# sa-22c-microsemi-powerboard.net
KiCad netlist of a schematic drawn in EAGLE
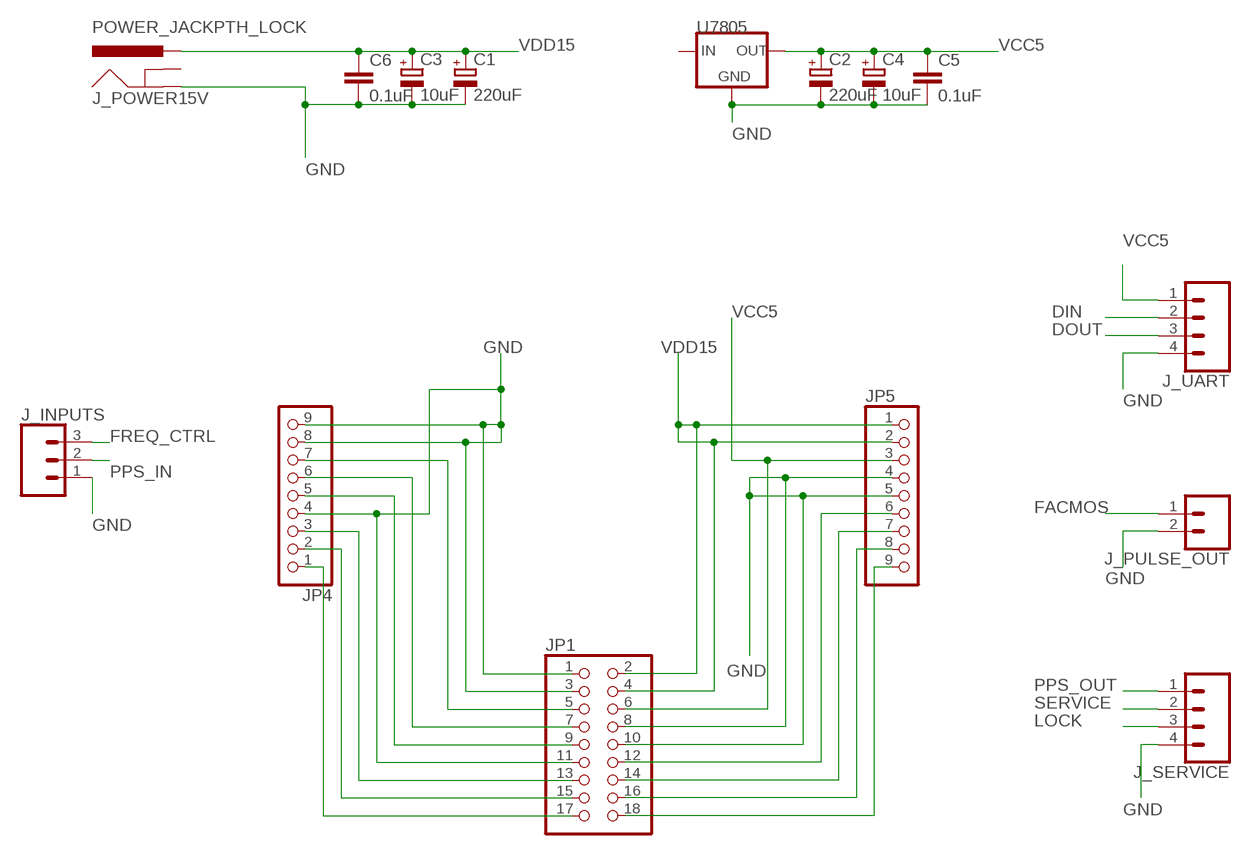
[diagram p0: schematic, sheet 1]

(export (version "E")
  (design (tool "Eeschema 10.0.6"))
  (components
    (comp (ref "C1")
      (value "220uF")
      (footprint "eagle-import:153CLV-1014")
      (libsource (lib "eagle-import") (part "CPOL-EU153CLV-1014"))
    )
    (comp (ref "C2")
      (value "220uF")
      (footprint "eagle-import:153CLV-1014")
      (libsource (lib "eagle-import") (part "CPOL-EU153CLV-1014"))
    )
    (comp (ref "C3")
      (value "10uF")
      (footprint "eagle-import:E2,5-6")
      (libsource (lib "eagle-import") (part "CPOL-EUE2.5-6"))
    )
    (comp (ref "C4")
      (value "10uF")
      (footprint "eagle-import:E2,5-6")
      (libsource (lib "eagle-import") (part "CPOL-EUE2.5-6"))
    )
    (comp (ref "C5")
      (value "0.1uF")
      (footprint "eagle-import:C050-024X044")
      (libsource (lib "eagle-import") (part "C-EU050-024X044"))
    )
    (comp (ref "C6")
      (value "0.1uF")
      (footprint "eagle-import:C050-024X044")
      (libsource (lib "eagle-import") (part "C-EU050-024X044"))
    )
    (comp (ref "JP1")
      (value "PINHD-2X9")
      (footprint "eagle-import:2X09")
      (libsource (lib "eagle-import") (part "PINHD-2X9"))
    )
    (comp (ref "JP4")
      (value "PINHD-1X9")
      (footprint "eagle-import:1X09")
      (libsource (lib "eagle-import") (part "PINHD-1X9"))
    )
    (comp (ref "JP5")
      (value "PINHD-1X9")
      (footprint "eagle-import:1X09")
      (libsource (lib "eagle-import") (part "PINHD-1X9"))
    )
    (comp (ref "J_INPUTS")
      (value "CONN_03LONGPADS")
      (footprint "eagle-import:1X03_LONGPADS")
      (libsource (lib "eagle-import") (part "CONN_03LONGPADS"))
    )
    (comp (ref "J_POWER15V")
      (value "POWER_JACKPTH_LOCK")
      (footprint "eagle-import:POWER_JACK_PTH_LOCK")
      (libsource (lib "eagle-import") (part "POWER_JACKPTH_LOCK"))
    )
    (comp (ref "J_PULSE_OUT")
      (value "CONN_02LOCK_LONGPADS")
      (footprint "eagle-import:1X02_LOCK_LONGPADS")
      (libsource (lib "eagle-import") (part "CONN_02LOCK_LONGPADS"))
    )
    (comp (ref "J_SERVICE")
      (value "CONN_04LONGPADS")
      (footprint "eagle-import:1X04_LONGPADS")
      (libsource (lib "eagle-import") (part "CONN_04LONGPADS"))
    )
    (comp (ref "J_UART")
      (value "CONN_04LONGPADS")
      (footprint "eagle-import:1X04_LONGPADS")
      (libsource (lib "eagle-import") (part "CONN_04LONGPADS"))
    )
    (comp (ref "U7805")
      (value "V_REG_78XXSINK")
      (footprint "eagle-import:TO220-IGO")
      (libsource (lib "eagle-import") (part "V_REG_78XXSINK"))
    )
  )
  (nets
    (net (code "1") (name "/DIN") (class "Default")
      (node (ref "J_UART") (pin "2") (pinfunction "2_2") (pintype "passive"))
    )
    (net (code "2") (name "/DOUT") (class "Default")
      (node (ref "J_UART") (pin "3") (pinfunction "3_3") (pintype "passive"))
    )
    (net (code "3") (name "/FACMOS") (class "Default")
      (node (ref "J_PULSE_OUT") (pin "1") (pinfunction "1_1") (pintype "passive"))
    )
    (net (code "4") (name "/FREQ_CTRL") (class "Default")
      (node (ref "J_INPUTS") (pin "3") (pinfunction "3_3") (pintype "passive"))
    )
    (net (code "5") (name "/GND") (class "Default")
      (node (ref "C1") (pin "-") (pinfunction "-_-") (pintype "passive"))
      (node (ref "C2") (pin "-") (pinfunction "-_-") (pintype "passive"))
      (node (ref "C3") (pin "-") (pinfunction "-_-") (pintype "passive"))
      (node (ref "C4") (pin "-") (pinfunction "-_-") (pintype "passive"))
      (node (ref "C5") (pin "2") (pinfunction "2_2") (pintype "passive"))
      (node (ref "C6") (pin "2") (pinfunction "2_2") (pintype "passive"))
      (node (ref "JP1") (pin "1") (pinfunction "1_1") (pintype "passive"))
      (node (ref "JP1") (pin "10") (pinfunction "10_10") (pintype "passive"))
      (node (ref "JP1") (pin "11") (pinfunction "11_11") (pintype "passive"))
      (node (ref "JP1") (pin "3") (pinfunction "3_3") (pintype "passive"))
      (node (ref "JP1") (pin "8") (pinfunction "8_8") (pintype "passive"))
      (node (ref "JP4") (pin "4") (pinfunction "4_4") (pintype "passive"))
      (node (ref "JP4") (pin "8") (pinfunction "8_8") (pintype "passive"))
      (node (ref "JP4") (pin "9") (pinfunction "9_9") (pintype "passive"))
      (node (ref "JP5") (pin "4") (pinfunction "4_4") (pintype "passive"))
      (node (ref "JP5") (pin "5") (pinfunction "5_5") (pintype "passive"))
      (node (ref "J_INPUTS") (pin "1") (pinfunction "1_1") (pintype "passive"))
      (node (ref "J_POWER15V") (pin "GND") (pinfunction "GND_GND") (pintype "bidirectional"))
      (node (ref "J_PULSE_OUT") (pin "2") (pinfunction "2_2") (pintype "passive"))
      (node (ref "J_SERVICE") (pin "4") (pinfunction "4_4") (pintype "passive"))
      (node (ref "J_UART") (pin "4") (pinfunction "4_4") (pintype "passive"))
      (node (ref "U7805") (pin "GND") (pinfunction "GND_GND") (pintype "input"))
    )
    (net (code "6") (name "/LOCK") (class "Default")
      (node (ref "J_SERVICE") (pin "3") (pinfunction "3_3") (pintype "passive"))
    )
    (net (code "7") (name "/PPS_IN") (class "Default")
      (node (ref "J_INPUTS") (pin "2") (pinfunction "2_2") (pintype "passive"))
    )
    (net (code "8") (name "/PPS_OUT") (class "Default")
      (node (ref "J_SERVICE") (pin "1") (pinfunction "1_1") (pintype "passive"))
    )
    (net (code "9") (name "/SERVICE") (class "Default")
      (node (ref "J_SERVICE") (pin "2") (pinfunction "2_2") (pintype "passive"))
    )
    (net (code "10") (name "/VCC5") (class "Default")
      (node (ref "C2") (pin "+") (pinfunction "+_+") (pintype "passive"))
      (node (ref "C4") (pin "+") (pinfunction "+_+") (pintype "passive"))
      (node (ref "C5") (pin "1") (pinfunction "1_1") (pintype "passive"))
      (node (ref "JP1") (pin "6") (pinfunction "6_6") (pintype "passive"))
      (node (ref "JP5") (pin "3") (pinfunction "3_3") (pintype "passive"))
      (node (ref "J_UART") (pin "1") (pinfunction "1_1") (pintype "passive"))
      (node (ref "U7805") (pin "OUT") (pinfunction "OUT_OUT") (pintype "passive"))
    )
    (net (code "11") (name "/VDD15") (class "Default")
      (node (ref "C1") (pin "+") (pinfunction "+_+") (pintype "passive"))
      (node (ref "C3") (pin "+") (pinfunction "+_+") (pintype "passive"))
      (node (ref "C6") (pin "1") (pinfunction "1_1") (pintype "passive"))
      (node (ref "JP1") (pin "2") (pinfunction "2_2") (pintype "passive"))
      (node (ref "JP1") (pin "4") (pinfunction "4_4") (pintype "passive"))
      (node (ref "JP5") (pin "1") (pinfunction "1_1") (pintype "passive"))
      (node (ref "JP5") (pin "2") (pinfunction "2_2") (pintype "passive"))
      (node (ref "J_POWER15V") (pin "PWR") (pinfunction "PWR_PWR") (pintype "bidirectional"))
    )
    (net (code "12") (name "Net-(JP1-Pad5)") (class "Default")
      (node (ref "JP1") (pin "5") (pinfunction "5_5") (pintype "passive"))
      (node (ref "JP4") (pin "7") (pinfunction "7_7") (pintype "passive"))
    )
    (net (code "13") (name "Net-(JP1-Pad7)") (class "Default")
      (node (ref "JP1") (pin "7") (pinfunction "7_7") (pintype "passive"))
      (node (ref "JP4") (pin "6") (pinfunction "6_6") (pintype "passive"))
    )
    (net (code "14") (name "Net-(JP1-Pad9)") (class "Default")
      (node (ref "JP1") (pin "9") (pinfunction "9_9") (pintype "passive"))
      (node (ref "JP4") (pin "5") (pinfunction "5_5") (pintype "passive"))
    )
    (net (code "15") (name "Net-(JP1-Pad12)") (class "Default")
      (node (ref "JP1") (pin "12") (pinfunction "12_12") (pintype "passive"))
      (node (ref "JP5") (pin "6") (pinfunction "6_6") (pintype "passive"))
    )
    (net (code "16") (name "Net-(JP1-Pad13)") (class "Default")
      (node (ref "JP1") (pin "13") (pinfunction "13_13") (pintype "passive"))
      (node (ref "JP4") (pin "3") (pinfunction "3_3") (pintype "passive"))
    )
    (net (code "17") (name "Net-(JP1-Pad14)") (class "Default")
      (node (ref "JP1") (pin "14") (pinfunction "14_14") (pintype "passive"))
      (node (ref "JP5") (pin "7") (pinfunction "7_7") (pintype "passive"))
    )
    (net (code "18") (name "Net-(JP1-Pad15)") (class "Default")
      (node (ref "JP1") (pin "15") (pinfunction "15_15") (pintype "passive"))
      (node (ref "JP4") (pin "2") (pinfunction "2_2") (pintype "passive"))
    )
    (net (code "19") (name "Net-(JP1-Pad16)") (class "Default")
      (node (ref "JP1") (pin "16") (pinfunction "16_16") (pintype "passive"))
      (node (ref "JP5") (pin "8") (pinfunction "8_8") (pintype "passive"))
    )
    (net (code "20") (name "Net-(JP1-Pad17)") (class "Default")
      (node (ref "JP1") (pin "17") (pinfunction "17_17") (pintype "passive"))
      (node (ref "JP4") (pin "1") (pinfunction "1_1") (pintype "passive"))
    )
    (net (code "21") (name "Net-(JP1-Pad18)") (class "Default")
      (node (ref "JP1") (pin "18") (pinfunction "18_18") (pintype "passive"))
      (node (ref "JP5") (pin "9") (pinfunction "9_9") (pintype "passive"))
    )
    (net (code "22") (name "unconnected-(J_POWER15V-PadGNDBREAK)") (class "Default")
      (node (ref "J_POWER15V") (pin "GNDBREAK") (pinfunction "GNDBREAK_GNDBREAK") (pintype "bidirectional"))
    )
    (net (code "23") (name "unconnected-(U7805-PadIN)") (class "Default")
      (node (ref "U7805") (pin "IN") (pinfunction "IN_IN") (pintype "input"))
    )
  )
)
